# switch.net
KiCad netlist of a schematic drawn in EAGLE
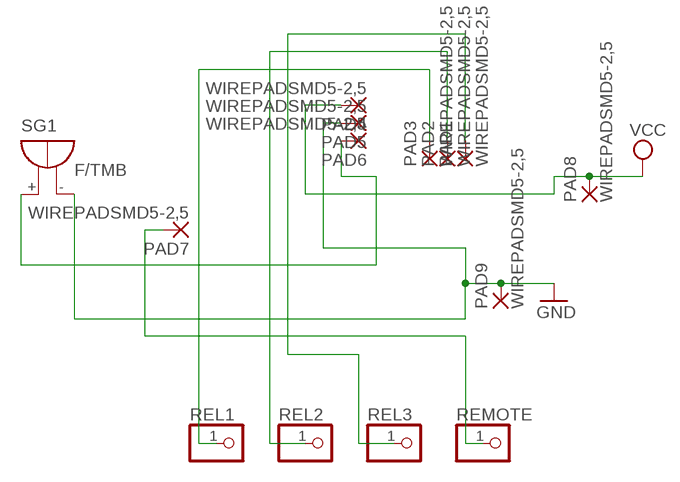
[diagram p0: schematic, sheet 1]

(export (version "E")
  (design (tool "Eeschema 10.0.6"))
  (components
    (comp (ref "PAD1")
      (value "WIREPADSMD5-2,5")
      (footprint "eagle-import:5-2,5")
      (libsource (lib "eagle-import") (part "WIREPADSMD5-2,5"))
    )
    (comp (ref "PAD2")
      (value "WIREPADSMD5-2,5")
      (footprint "eagle-import:5-2,5")
      (libsource (lib "eagle-import") (part "WIREPADSMD5-2,5"))
    )
    (comp (ref "PAD3")
      (value "WIREPADSMD5-2,5")
      (footprint "eagle-import:5-2,5")
      (libsource (lib "eagle-import") (part "WIREPADSMD5-2,5"))
    )
    (comp (ref "PAD4")
      (value "WIREPADSMD5-2,5")
      (footprint "eagle-import:5-2,5")
      (libsource (lib "eagle-import") (part "WIREPADSMD5-2,5"))
    )
    (comp (ref "PAD5")
      (value "WIREPADSMD5-2,5")
      (footprint "eagle-import:5-2,5")
      (libsource (lib "eagle-import") (part "WIREPADSMD5-2,5"))
    )
    (comp (ref "PAD6")
      (value "WIREPADSMD5-2,5")
      (footprint "eagle-import:5-2,5")
      (libsource (lib "eagle-import") (part "WIREPADSMD5-2,5"))
    )
    (comp (ref "PAD7")
      (value "WIREPADSMD5-2,5")
      (footprint "eagle-import:5-2,5")
      (libsource (lib "eagle-import") (part "WIREPADSMD5-2,5"))
    )
    (comp (ref "PAD8")
      (value "WIREPADSMD5-2,5")
      (footprint "eagle-import:5-2,5")
      (libsource (lib "eagle-import") (part "WIREPADSMD5-2,5"))
    )
    (comp (ref "PAD9")
      (value "WIREPADSMD5-2,5")
      (footprint "eagle-import:5-2,5")
      (libsource (lib "eagle-import") (part "WIREPADSMD5-2,5"))
    )
    (comp (ref "REL1")
      (value "PINHD-1X1")
      (footprint "eagle-import:1X01")
      (libsource (lib "eagle-import") (part "PINHD-1X1"))
    )
    (comp (ref "REL2")
      (value "PINHD-1X1")
      (footprint "eagle-import:1X01")
      (libsource (lib "eagle-import") (part "PINHD-1X1"))
    )
    (comp (ref "REL3")
      (value "PINHD-1X1")
      (footprint "eagle-import:1X01")
      (libsource (lib "eagle-import") (part "PINHD-1X1"))
    )
    (comp (ref "REMOTE")
      (value "PINHD-1X1")
      (footprint "eagle-import:1X01")
      (libsource (lib "eagle-import") (part "PINHD-1X1"))
    )
    (comp (ref "SG1")
      (value "F/TMB")
      (footprint "eagle-import:F_TMB")
      (libsource (lib "eagle-import") (part "F/TMB"))
    )
  )
  (nets
    (net (code "1") (name "GND") (class "Default")
      (node (ref "PAD5") (pin "1") (pinfunction "P_1") (pintype "passive"))
      (node (ref "PAD9") (pin "1") (pinfunction "P_1") (pintype "passive"))
      (node (ref "SG1") (pin "-") (pinfunction "-_-") (pintype "passive"))
    )
    (net (code "2") (name "Net-(PAD1-P)") (class "Default")
      (node (ref "PAD1") (pin "1") (pinfunction "P_1") (pintype "passive"))
      (node (ref "REL3") (pin "1") (pinfunction "1_1") (pintype "passive"))
    )
    (net (code "3") (name "Net-(PAD2-P)") (class "Default")
      (node (ref "PAD2") (pin "1") (pinfunction "P_1") (pintype "passive"))
      (node (ref "REL2") (pin "1") (pinfunction "1_1") (pintype "passive"))
    )
    (net (code "4") (name "Net-(PAD3-P)") (class "Default")
      (node (ref "PAD3") (pin "1") (pinfunction "P_1") (pintype "passive"))
      (node (ref "REL1") (pin "1") (pinfunction "1_1") (pintype "passive"))
    )
    (net (code "5") (name "Net-(PAD6-P)") (class "Default")
      (node (ref "PAD6") (pin "1") (pinfunction "P_1") (pintype "passive"))
      (node (ref "SG1") (pin "+") (pinfunction "+_+") (pintype "passive"))
    )
    (net (code "6") (name "Net-(PAD7-P)") (class "Default")
      (node (ref "PAD7") (pin "1") (pinfunction "P_1") (pintype "passive"))
      (node (ref "REMOTE") (pin "1") (pinfunction "1_1") (pintype "passive"))
    )
    (net (code "7") (name "VCC") (class "Default")
      (node (ref "PAD4") (pin "1") (pinfunction "P_1") (pintype "passive"))
      (node (ref "PAD8") (pin "1") (pinfunction "P_1") (pintype "passive"))
    )
  )
)
